# radio-module.net
KiCad netlist of a schematic drawn in Altium Designer
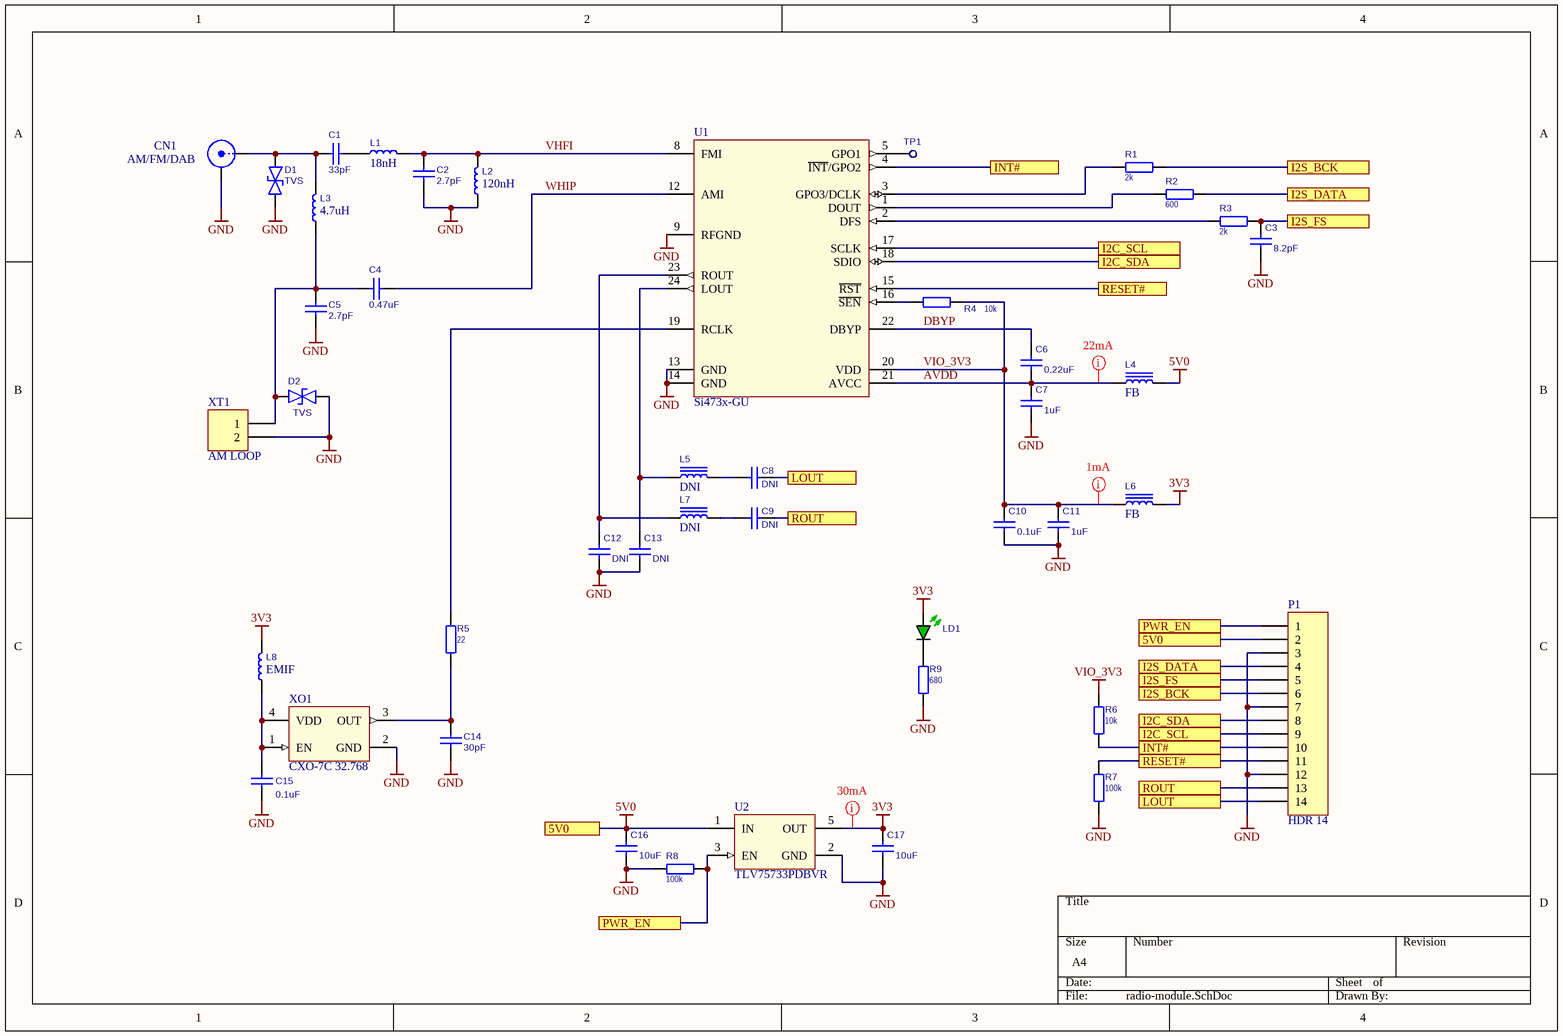
[diagram p0: radio-module.SchDoc]

(export (version "E")
  (design (tool "Eeschema 10.0.6"))
  (components
    (comp (ref "C1")
      (value "33pF")
      (footprint "Capacitors:C0603")
      (description "CAP_NPOL")
      (fields (field (name "Comment") "06035A330JAT2A"))
      (libsource (lib "capacitors") (part "CAP_NPOL"))
    )
    (comp (ref "C2")
      (value "2.7pF")
      (footprint "Capacitors:C0603")
      (description "CAP_NPOL")
      (fields (field (name "Comment") "GCM1885C2A2R7BA16D"))
      (libsource (lib "capacitors") (part "CAP_NPOL"))
    )
    (comp (ref "C3")
      (value "8.2pF")
      (footprint "Capacitors:C0603")
      (description "CAP_NPOL")
      (libsource (lib "capacitors") (part "CAP_NPOL"))
    )
    (comp (ref "C4")
      (value "0.47uF")
      (footprint "Capacitors:C0603")
      (description "CAP_NPOL")
      (libsource (lib "capacitors") (part "CAP_NPOL"))
    )
    (comp (ref "C5")
      (value "2.7pF")
      (footprint "Capacitors:C0603")
      (description "CAP_NPOL")
      (fields (field (name "Comment") "GCM1885C2A2R7BA16D"))
      (libsource (lib "capacitors") (part "CAP_NPOL"))
    )
    (comp (ref "C6")
      (value "0.22uF")
      (footprint "Capacitors:C0603")
      (description "CAP_NPOL")
      (libsource (lib "capacitors") (part "CAP_NPOL"))
    )
    (comp (ref "C7")
      (value "1uF")
      (footprint "Capacitors:C0603")
      (description "CAP_NPOL")
      (libsource (lib "capacitors") (part "CAP_NPOL"))
    )
    (comp (ref "C8")
      (value "DNI")
      (footprint "Capacitors:C0603")
      (description "CAP_NPOL")
      (fields (field (name "Comment") "0.1uF"))
      (libsource (lib "capacitors") (part "CAP_NPOL"))
    )
    (comp (ref "C9")
      (value "DNI")
      (footprint "Capacitors:C0603")
      (description "CAP_NPOL")
      (fields (field (name "Comment") "0.1uF"))
      (libsource (lib "capacitors") (part "CAP_NPOL"))
    )
    (comp (ref "C10")
      (value "0.1uF")
      (footprint "Capacitors:C0603")
      (description "CAP_NPOL")
      (libsource (lib "capacitors") (part "CAP_NPOL"))
    )
    (comp (ref "C11")
      (value "1uF")
      (footprint "Capacitors:C0603")
      (description "CAP_NPOL")
      (libsource (lib "capacitors") (part "CAP_NPOL"))
    )
    (comp (ref "C12")
      (value "DNI")
      (footprint "Capacitors:C0603")
      (description "CAP_NPOL")
      (fields (field (name "Comment") "8.2pF"))
      (libsource (lib "capacitors") (part "CAP_NPOL"))
    )
    (comp (ref "C13")
      (value "DNI")
      (footprint "Capacitors:C0603")
      (description "CAP_NPOL")
      (fields (field (name "Comment") "8.2pF"))
      (libsource (lib "capacitors") (part "CAP_NPOL"))
    )
    (comp (ref "C14")
      (value "30pF")
      (footprint "C0603")
      (description "CAP_NPOL")
      (libsource (lib "capacitors") (part "CAP_NPOL"))
    )
    (comp (ref "C15")
      (value "0.1uF")
      (footprint "Capacitors:C0603")
      (description "CAP_NPOL")
      (fields (field (name "Comment") "CC0603KRX7R9BB104"))
      (libsource (lib "capacitors") (part "CAP_NPOL"))
    )
    (comp (ref "C16")
      (value "10uF")
      (footprint "Capacitors:C0603")
      (description "CAP_NPOL")
      (libsource (lib "capacitors") (part "CAP_NPOL"))
    )
    (comp (ref "C17")
      (value "10uF")
      (footprint "Capacitors:C0603")
      (description "CAP_NPOL")
      (libsource (lib "capacitors") (part "CAP_NPOL"))
    )
    (comp (ref "CN1")
      (value "SMB")
      (footprint "SMB_V-RJ45")
      (description "SMB Straight Connector")
      (fields (field (name "PUBLISHER") "Altium Limited"))
      (libsource (lib "Miscellaneous Connectors") (part "SMB"))
    )
    (comp (ref "D1")
      (value "TVS")
      (footprint "SOD-323")
      (description "TVS Diodes")
      (fields (field (name "Comment") "CDSOD323-T05LC"))
      (libsource (lib "diodes") (part "TVS_BIDIR"))
    )
    (comp (ref "D2")
      (value "TVS")
      (footprint "SOD-323")
      (description "TVS Diodes")
      (fields (field (name "Comment") "CDSOD323-T05LC"))
      (libsource (lib "diodes") (part "TVS_BIDIR"))
    )
    (comp (ref "L1")
      (value "18nH")
      (footprint "IND0603")
      (description "IND_WO_IRON")
      (fields (field (name "Comment") "LQW18AN18NJ0ZD"))
      (libsource (lib "inductors") (part "IND_WO_IRON"))
    )
    (comp (ref "L2")
      (value "120nH")
      (footprint "IND0603")
      (description "IND_WO_IRON")
      (fields (field (name "Comment") "LQW18ANR12J00D"))
      (libsource (lib "inductors") (part "IND_WO_IRON"))
    )
    (comp (ref "L3")
      (value "4.7uH")
      (footprint "IND0603")
      (description "IND_WO_IRON")
      (fields (field (name "Comment") "CIL 10J 4R7"))
      (libsource (lib "inductors") (part "IND_WO_IRON"))
    )
    (comp (ref "L4")
      (value "FB")
      (footprint "IND0603")
      (description "IND_W_IRON")
      (fields (field (name "Comment") "BLM18AG102SN1D"))
      (libsource (lib "inductors") (part "IND_W_IRON"))
    )
    (comp (ref "L5")
      (value "DNI")
      (footprint "IND0603")
      (description "IND_W_IRON")
      (fields (field (name "Comment") "BLM18AG102SN1D"))
      (libsource (lib "inductors") (part "IND_W_IRON"))
    )
    (comp (ref "L6")
      (value "FB")
      (footprint "IND0603")
      (description "IND_W_IRON")
      (fields (field (name "Comment") "BLM18AG102SN1D"))
      (libsource (lib "inductors") (part "IND_W_IRON"))
    )
    (comp (ref "L7")
      (value "DNI")
      (footprint "IND0603")
      (description "IND_W_IRON")
      (fields (field (name "Comment") "BLM18AG102SN1D"))
      (libsource (lib "inductors") (part "IND_W_IRON"))
    )
    (comp (ref "L8")
      (value "EMIF")
      (footprint "IND0603")
      (description "IND_WO_IRON")
      (fields (field (name "Comment") "BLM18AG102SN1D"))
      (libsource (lib "") (part "IND_WO_IRON_1"))
    )
    (comp (ref "LD1")
      (value "LED_G")
      (footprint "Resistors:R0603")
      (description "LED Green")
      (libsource (lib "leds") (part "LED_GREEN"))
    )
    (comp (ref "P1")
      (value "HDR 14")
      (footprint "PLS-14")
      (description "Header, 14-Pin")
      (fields (field (name "PUBLISHER") "Altium Limited"))
      (libsource (lib "HDR") (part "HDR 14"))
    )
    (comp (ref "R1")
      (value "2k")
      (footprint "Resistors:R0603")
      (description "RES")
      (libsource (lib "resistors") (part "RESISTOR"))
    )
    (comp (ref "R2")
      (value "600")
      (footprint "Resistors:R0603")
      (description "RES")
      (libsource (lib "resistors") (part "RESISTOR"))
    )
    (comp (ref "R3")
      (value "2k")
      (footprint "Resistors:R0603")
      (description "RES")
      (libsource (lib "resistors") (part "RESISTOR"))
    )
    (comp (ref "R4")
      (value "10k")
      (footprint "Resistors:R0603")
      (description "RES")
      (libsource (lib "resistors") (part "RESISTOR"))
    )
    (comp (ref "R5")
      (value "22")
      (footprint "R0603")
      (description "RES")
      (libsource (lib "resistors") (part "RESISTOR"))
    )
    (comp (ref "R6")
      (value "10k")
      (footprint "Resistors:R0603")
      (description "RES")
      (libsource (lib "resistors") (part "RESISTOR"))
    )
    (comp (ref "R7")
      (value "100k")
      (footprint "Resistors:R0603")
      (description "RES")
      (libsource (lib "resistors") (part "RESISTOR"))
    )
    (comp (ref "R8")
      (value "100k")
      (footprint "Resistors:R0603")
      (description "RES")
      (libsource (lib "resistors") (part "RESISTOR"))
    )
    (comp (ref "R9")
      (value "680")
      (footprint "Resistors:R0603")
      (description "RES")
      (libsource (lib "resistors") (part "RESISTOR"))
    )
    (comp (ref "TP1")
      (value "TEST-POINT")
      (footprint "PAD")
      (description "PCB terminal block")
      (libsource (lib "TestPoint") (part "TEST-POINT"))
    )
    (comp (ref "U1")
      (value "Si473x-GU")
      (footprint "SSOP-24")
      (description "BROADCAST AM/FM/SW/LW RADIO RECEIVER")
      (libsource (lib "Si473x") (part "Si473x-GU"))
    )
    (comp (ref "U2")
      (value "TLV75733PDBVR")
      (footprint "SOT-23-5")
      (description "Capacitor-Free, 1A, Low-Dropout Regulator with Foldback Current Limit for Portable Devices")
      (libsource (lib "TLV733P") (part "TLV733P"))
    )
    (comp (ref "XO1")
      (value "CXO-7C 32.768")
      (footprint "CXO-5032")
      (libsource (lib "Oscillator") (part "CXO-7C"))
    )
    (comp (ref "XT1")
      (value "AM LOOP")
      (footprint "PLS-2")
      (description "Header, 2-Pin")
      (fields (field (name "PUBLISHER") "Altium Limited"))
      (libsource (lib "HDR") (part "HDR 2"))
    )
  )
  (nets
    (net (code "1") (name "/AVDD") (class "Default")
      (node (ref "C6") (pin "2") (pinfunction "2_2") (pintype "passive"))
      (node (ref "C7") (pin "1") (pinfunction "1_1") (pintype "passive"))
      (node (ref "L4") (pin "1") (pintype "passive"))
      (node (ref "U1") (pin "21") (pinfunction "AVCC_21") (pintype "power_in"))
    )
    (net (code "2") (name "/DBYP") (class "Default")
      (node (ref "C6") (pin "1") (pinfunction "1_1") (pintype "passive"))
      (node (ref "U1") (pin "22") (pinfunction "DBYP_22") (pintype "passive"))
    )
    (net (code "3") (name "/I2C_SCL") (class "Default")
      (node (ref "P1") (pin "9") (pinfunction "9_9") (pintype "passive"))
      (node (ref "U1") (pin "17") (pinfunction "SCLK_17") (pintype "input"))
    )
    (net (code "4") (name "/I2C_SDA") (class "Default")
      (node (ref "P1") (pin "8") (pinfunction "8_8") (pintype "passive"))
      (node (ref "U1") (pin "18") (pinfunction "SDIO_18") (pintype "bidirectional"))
    )
    (net (code "5") (name "/I2S_BCK") (class "Default")
      (node (ref "P1") (pin "6") (pinfunction "6_6") (pintype "passive"))
      (node (ref "R1") (pin "1") (pinfunction "1_1") (pintype "passive"))
    )
    (net (code "6") (name "/I2S_DATA") (class "Default")
      (node (ref "P1") (pin "4") (pinfunction "4_4") (pintype "passive"))
      (node (ref "R2") (pin "1") (pinfunction "1_1") (pintype "passive"))
    )
    (net (code "7") (name "/I2S_FS") (class "Default")
      (node (ref "C3") (pin "1") (pinfunction "1_1") (pintype "passive"))
      (node (ref "P1") (pin "5") (pinfunction "5_5") (pintype "passive"))
      (node (ref "R3") (pin "1") (pinfunction "1_1") (pintype "passive"))
    )
    (net (code "8") (name "/INT#") (class "Default")
      (node (ref "P1") (pin "10") (pinfunction "10_10") (pintype "passive"))
      (node (ref "R6") (pin "2") (pinfunction "2_2") (pintype "passive"))
      (node (ref "U1") (pin "4") (pinfunction "~{INT}/GPO2_4") (pintype "output"))
    )
    (net (code "9") (name "/LOUT") (class "Default")
      (node (ref "C8") (pin "2") (pinfunction "2_2") (pintype "passive"))
      (node (ref "P1") (pin "14") (pinfunction "14_14") (pintype "passive"))
    )
    (net (code "10") (name "/PWR_EN") (class "Default")
      (node (ref "P1") (pin "1") (pinfunction "1_1") (pintype "passive"))
      (node (ref "R8") (pin "1") (pinfunction "1_1") (pintype "passive"))
      (node (ref "U2") (pin "3") (pinfunction "EN_3") (pintype "input"))
    )
    (net (code "11") (name "/RESET#") (class "Default")
      (node (ref "P1") (pin "11") (pinfunction "11_11") (pintype "passive"))
      (node (ref "R7") (pin "2") (pinfunction "2_2") (pintype "passive"))
      (node (ref "U1") (pin "15") (pinfunction "~{RST}_15") (pintype "input"))
    )
    (net (code "12") (name "/ROUT") (class "Default")
      (node (ref "C9") (pin "2") (pinfunction "2_2") (pintype "passive"))
      (node (ref "P1") (pin "13") (pinfunction "13_13") (pintype "passive"))
    )
    (net (code "13") (name "/VHFI") (class "Default")
      (node (ref "C2") (pin "2") (pinfunction "2_2") (pintype "passive"))
      (node (ref "L1") (pin "2") (pintype "passive"))
      (node (ref "L2") (pin "2") (pintype "passive"))
      (node (ref "U1") (pin "8") (pinfunction "FMI_8") (pintype "passive"))
    )
    (net (code "14") (name "/WHIP") (class "Default")
      (node (ref "C4") (pin "1") (pinfunction "1_1") (pintype "passive"))
      (node (ref "U1") (pin "12") (pinfunction "AMI_12") (pintype "passive"))
    )
    (net (code "15") (name "3V3") (class "Default")
      (node (ref "C17") (pin "1") (pinfunction "1_1") (pintype "passive"))
      (node (ref "L6") (pin "2") (pintype "passive"))
      (node (ref "L8") (pin "1") (pintype "passive"))
      (node (ref "LD1") (pin "2") (pintype "passive"))
      (node (ref "U2") (pin "5") (pinfunction "OUT_5") (pintype "power_in"))
    )
    (net (code "16") (name "5V0") (class "Default")
      (node (ref "C16") (pin "1") (pinfunction "1_1") (pintype "passive"))
      (node (ref "L4") (pin "2") (pintype "passive"))
      (node (ref "P1") (pin "2") (pinfunction "2_2") (pintype "passive"))
      (node (ref "U2") (pin "1") (pinfunction "IN_1") (pintype "power_in"))
    )
    (net (code "17") (name "GND") (class "Default")
      (node (ref "C10") (pin "2") (pinfunction "2_2") (pintype "passive"))
      (node (ref "C11") (pin "2") (pinfunction "2_2") (pintype "passive"))
      (node (ref "C12") (pin "2") (pinfunction "2_2") (pintype "passive"))
      (node (ref "C13") (pin "2") (pinfunction "2_2") (pintype "passive"))
      (node (ref "C14") (pin "2") (pinfunction "2_2") (pintype "passive"))
      (node (ref "C15") (pin "1") (pinfunction "1_1") (pintype "passive"))
      (node (ref "C16") (pin "2") (pinfunction "2_2") (pintype "passive"))
      (node (ref "C17") (pin "2") (pinfunction "2_2") (pintype "passive"))
      (node (ref "C2") (pin "1") (pinfunction "1_1") (pintype "passive"))
      (node (ref "C3") (pin "2") (pinfunction "2_2") (pintype "passive"))
      (node (ref "C5") (pin "1") (pinfunction "1_1") (pintype "passive"))
      (node (ref "C7") (pin "2") (pinfunction "2_2") (pintype "passive"))
      (node (ref "CN1") (pin "2") (pinfunction "Y_2") (pintype "passive"))
      (node (ref "D1") (pin "1") (pinfunction "1_1") (pintype "passive"))
      (node (ref "D2") (pin "1") (pinfunction "1_1") (pintype "passive"))
      (node (ref "L2") (pin "1") (pintype "passive"))
      (node (ref "P1") (pin "12") (pinfunction "12_12") (pintype "passive"))
      (node (ref "P1") (pin "3") (pinfunction "3_3") (pintype "passive"))
      (node (ref "P1") (pin "7") (pinfunction "7_7") (pintype "passive"))
      (node (ref "R7") (pin "1") (pinfunction "1_1") (pintype "passive"))
      (node (ref "R8") (pin "2") (pinfunction "2_2") (pintype "passive"))
      (node (ref "R9") (pin "2") (pinfunction "2_2") (pintype "passive"))
      (node (ref "U1") (pin "13") (pinfunction "GND_13") (pintype "power_in"))
      (node (ref "U1") (pin "14") (pinfunction "GND_14") (pintype "power_in"))
      (node (ref "U1") (pin "9") (pinfunction "RFGND_9") (pintype "power_in"))
      (node (ref "U2") (pin "2") (pinfunction "GND_2") (pintype "power_in"))
      (node (ref "XO1") (pin "2") (pinfunction "GND_2") (pintype "power_in"))
      (node (ref "XT1") (pin "2") (pinfunction "2_2") (pintype "passive"))
    )
    (net (code "18") (name "Net-(C1-Pad1)") (class "Default")
      (node (ref "C1") (pin "1") (pinfunction "1_1") (pintype "passive"))
      (node (ref "L1") (pin "1") (pintype "passive"))
    )
    (net (code "19") (name "Net-(C4-Pad2)") (class "Default")
      (node (ref "C4") (pin "2") (pinfunction "2_2") (pintype "passive"))
      (node (ref "C5") (pin "2") (pinfunction "2_2") (pintype "passive"))
      (node (ref "D2") (pin "2") (pinfunction "2_2") (pintype "passive"))
      (node (ref "L3") (pin "1") (pintype "passive"))
      (node (ref "XT1") (pin "1") (pinfunction "1_1") (pintype "passive"))
    )
    (net (code "20") (name "Net-(C8-Pad1)") (class "Default")
      (node (ref "C8") (pin "1") (pinfunction "1_1") (pintype "passive"))
      (node (ref "L5") (pin "2") (pintype "passive"))
    )
    (net (code "21") (name "Net-(C9-Pad1)") (class "Default")
      (node (ref "C9") (pin "1") (pinfunction "1_1") (pintype "passive"))
      (node (ref "L7") (pin "2") (pintype "passive"))
    )
    (net (code "22") (name "Net-(CN1-X)") (class "Default")
      (node (ref "C1") (pin "2") (pinfunction "2_2") (pintype "passive"))
      (node (ref "CN1") (pin "1") (pinfunction "X_1") (pintype "passive"))
      (node (ref "D1") (pin "2") (pinfunction "2_2") (pintype "passive"))
      (node (ref "L3") (pin "2") (pintype "passive"))
    )
    (net (code "23") (name "Net-(LD1-Pad1)") (class "Default")
      (node (ref "LD1") (pin "1") (pintype "passive"))
      (node (ref "R9") (pin "1") (pinfunction "1_1") (pintype "passive"))
    )
    (net (code "24") (name "Net-(U1-DFS)") (class "Default")
      (node (ref "R3") (pin "2") (pinfunction "2_2") (pintype "passive"))
      (node (ref "U1") (pin "2") (pinfunction "DFS_2") (pintype "input"))
    )
    (net (code "25") (name "Net-(U1-DOUT)") (class "Default")
      (node (ref "R2") (pin "2") (pinfunction "2_2") (pintype "passive"))
      (node (ref "U1") (pin "1") (pinfunction "DOUT_1") (pintype "output"))
    )
    (net (code "26") (name "Net-(U1-GPO1)") (class "Default")
      (node (ref "TP1") (pin "1") (pinfunction "1_1") (pintype "passive"))
      (node (ref "U1") (pin "5") (pinfunction "GPO1_5") (pintype "output"))
    )
    (net (code "27") (name "Net-(U1-GPO3{slash}DCLK)") (class "Default")
      (node (ref "R1") (pin "2") (pinfunction "2_2") (pintype "passive"))
      (node (ref "U1") (pin "3") (pinfunction "GPO3/DCLK_3") (pintype "bidirectional"))
    )
    (net (code "28") (name "Net-(U1-LOUT)") (class "Default")
      (node (ref "C13") (pin "1") (pinfunction "1_1") (pintype "passive"))
      (node (ref "L5") (pin "1") (pintype "passive"))
      (node (ref "U1") (pin "24") (pinfunction "LOUT_24") (pintype "output"))
    )
    (net (code "29") (name "Net-(U1-RCLK)") (class "Default")
      (node (ref "R5") (pin "1") (pinfunction "1_1") (pintype "passive"))
      (node (ref "U1") (pin "19") (pinfunction "RCLK_19") (pintype "passive"))
    )
    (net (code "30") (name "Net-(U1-ROUT)") (class "Default")
      (node (ref "C12") (pin "1") (pinfunction "1_1") (pintype "passive"))
      (node (ref "L7") (pin "1") (pintype "passive"))
      (node (ref "U1") (pin "23") (pinfunction "ROUT_23") (pintype "output"))
    )
    (net (code "31") (name "Net-(U1-~{SEN})") (class "Default")
      (node (ref "R4") (pin "2") (pinfunction "2_2") (pintype "passive"))
      (node (ref "U1") (pin "16") (pinfunction "~{SEN}_16") (pintype "input"))
    )
    (net (code "32") (name "Net-(XO1-EN)") (class "Default")
      (node (ref "C15") (pin "2") (pinfunction "2_2") (pintype "passive"))
      (node (ref "L8") (pin "2") (pintype "passive"))
      (node (ref "XO1") (pin "1") (pinfunction "EN_1") (pintype "input"))
      (node (ref "XO1") (pin "4") (pinfunction "VDD_4") (pintype "power_in"))
    )
    (net (code "33") (name "Net-(XO1-OUT)") (class "Default")
      (node (ref "C14") (pin "1") (pinfunction "1_1") (pintype "passive"))
      (node (ref "R5") (pin "2") (pinfunction "2_2") (pintype "passive"))
      (node (ref "XO1") (pin "3") (pinfunction "OUT_3") (pintype "output"))
    )
    (net (code "34") (name "VIO_3V3") (class "Default")
      (node (ref "C10") (pin "1") (pinfunction "1_1") (pintype "passive"))
      (node (ref "C11") (pin "1") (pinfunction "1_1") (pintype "passive"))
      (node (ref "L6") (pin "1") (pintype "passive"))
      (node (ref "R4") (pin "1") (pinfunction "1_1") (pintype "passive"))
      (node (ref "R6") (pin "1") (pinfunction "1_1") (pintype "passive"))
      (node (ref "U1") (pin "20") (pinfunction "VDD_20") (pintype "power_in"))
    )
  )
)
